# MCU.net
KiCad netlist of a schematic drawn in Altium Designer
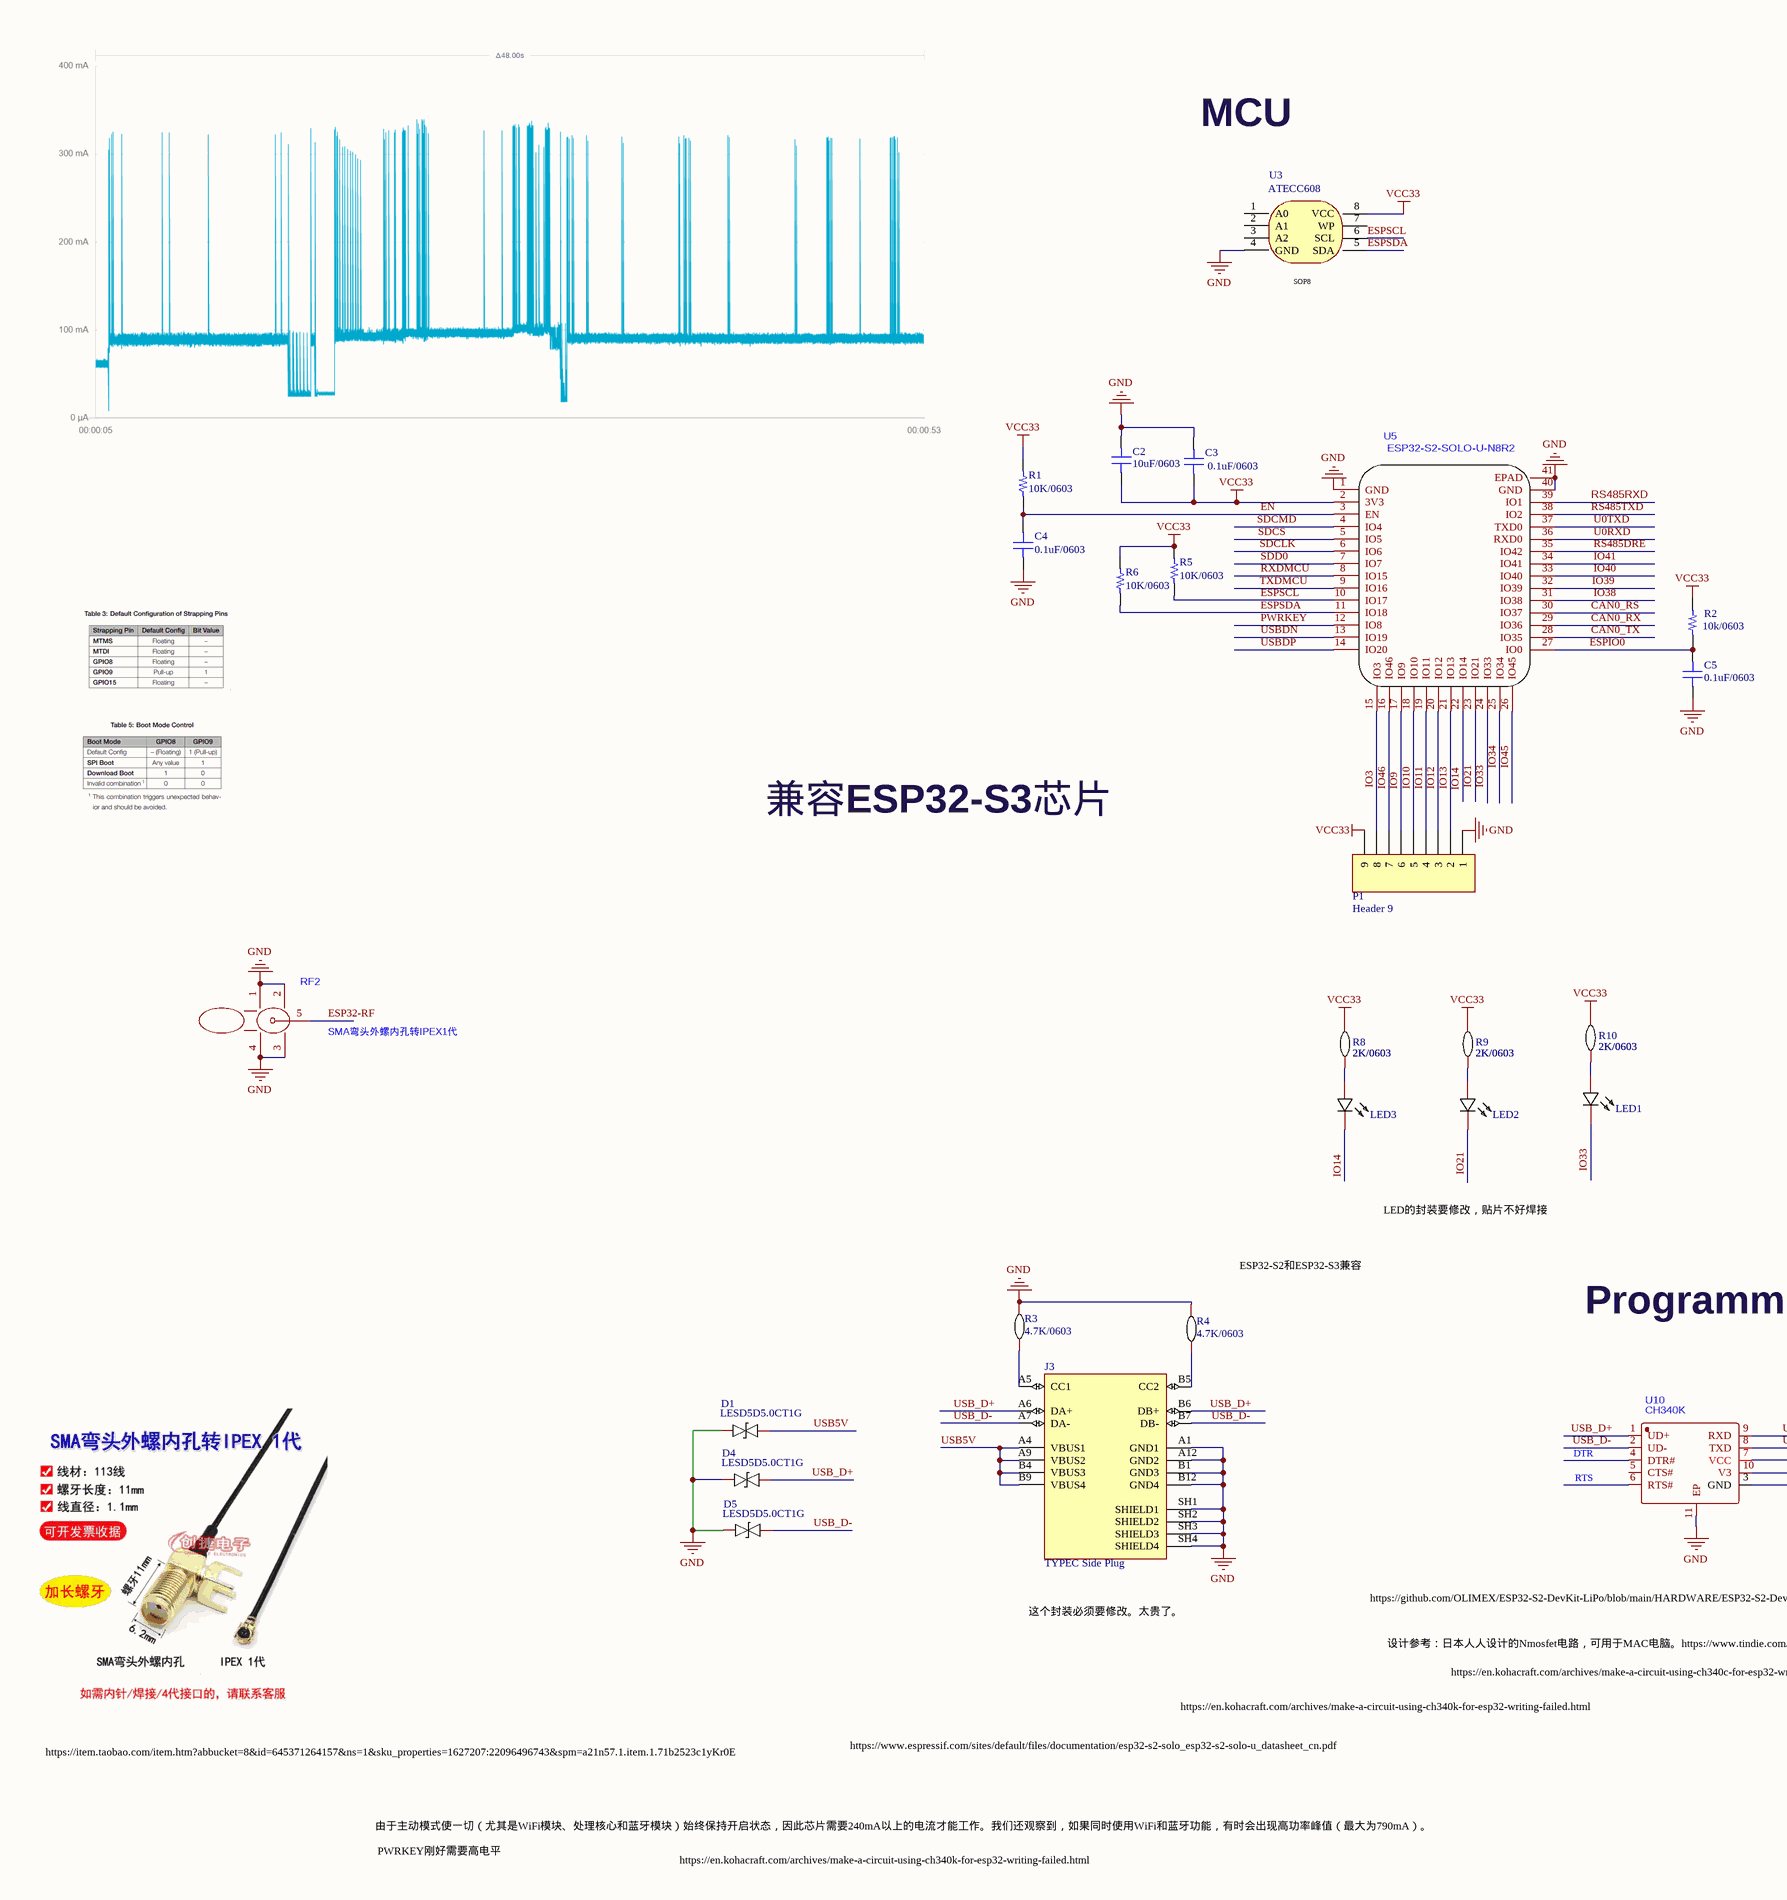
[diagram p0: MCU.SchDoc, left]
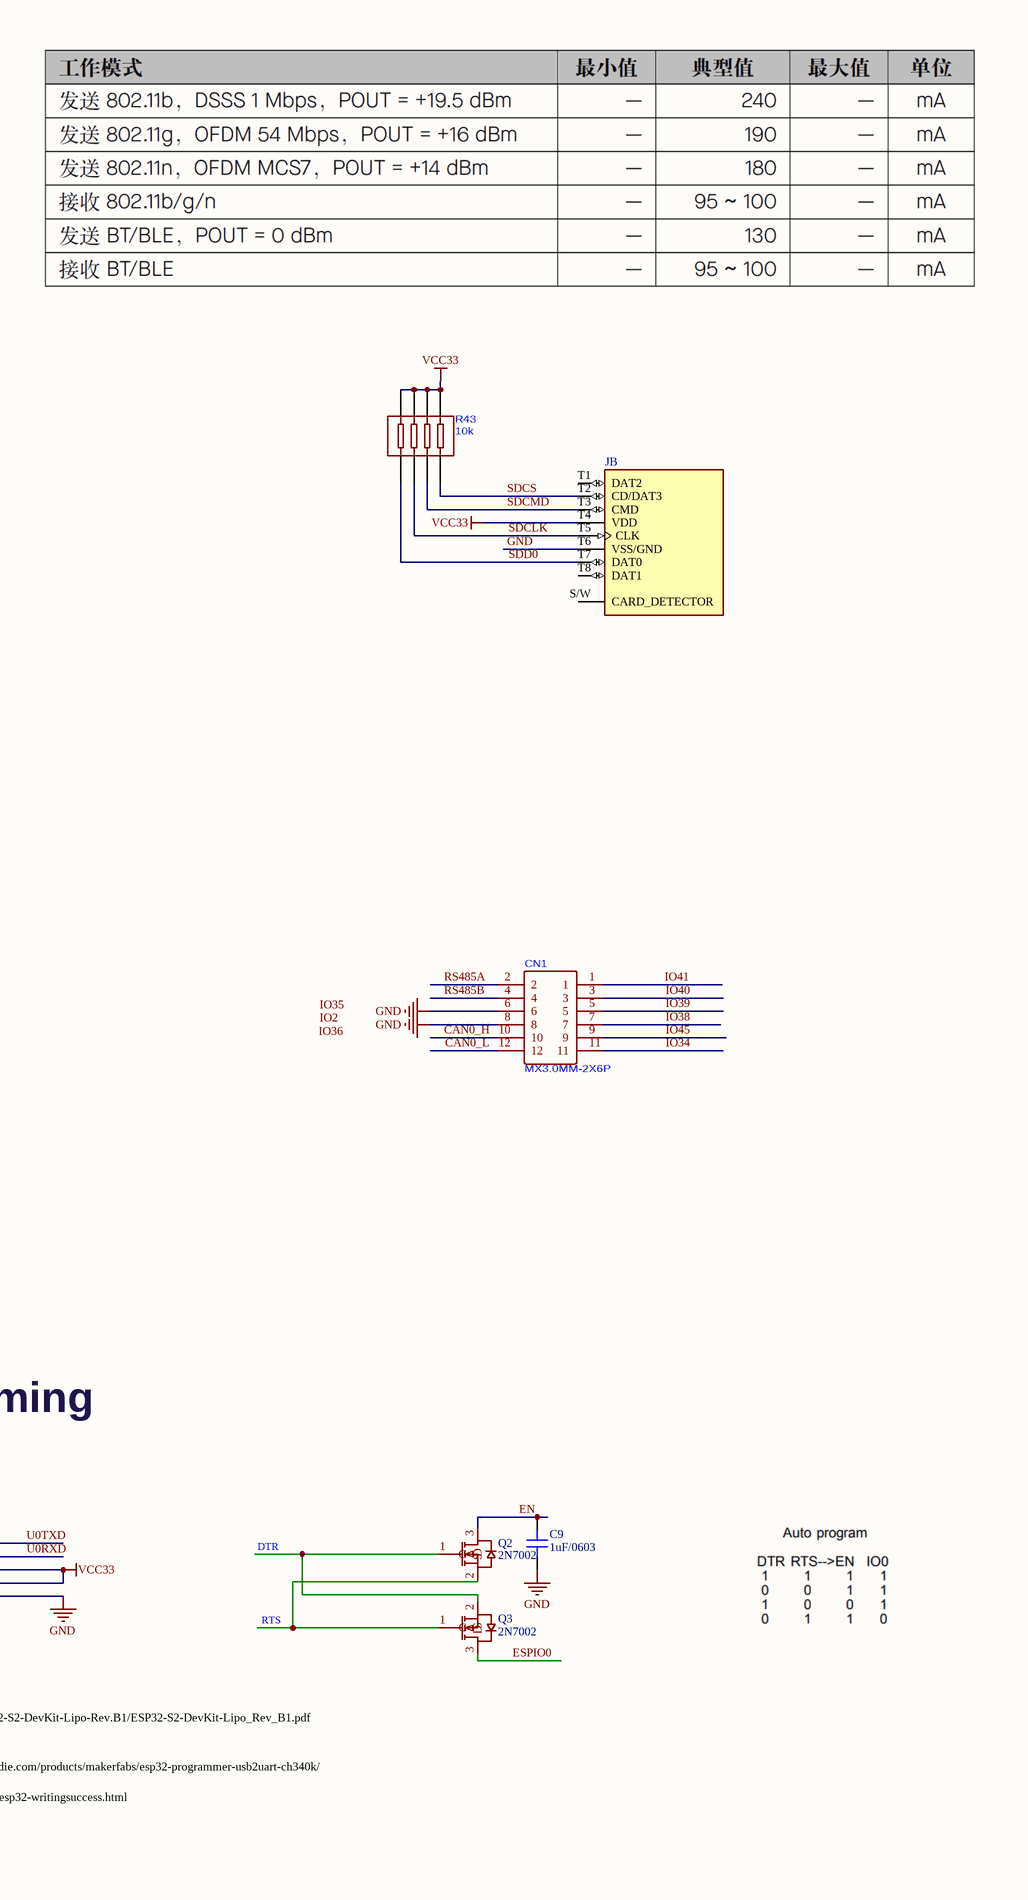
[diagram p1: MCU.SchDoc, right]

(export (version "E")
  (design (tool "Eeschema 10.0.6"))
  (components
    (comp (ref "C2")
      (value "10uF/0603")
      (footprint "CAP0603")
      (description "CAP CER SMD 0805 22PF 5% 50V X7R")
      (fields (field (name "PART NUMBER") "C0805C220J5RAC7800") (field (name "MANUFACTURER") "KEMET"))
      (libsource (lib "Celestial Altium Library - altium_library") (part "Capacitor"))
    )
    (comp (ref "C3")
      (value "0.1uF/0603")
      (footprint "CAp0603")
      (description "CAP CER SMD 0805 22PF 5% 50V X7R")
      (fields (field (name "PART NUMBER") "C0805C220J5RAC7800") (field (name "MANUFACTURER") "KEMET"))
      (libsource (lib "Celestial Altium Library - altium_library") (part "Capacitor"))
    )
    (comp (ref "C4")
      (value "0.1uF/0603")
      (footprint "CAP0603")
      (description "CAP CER SMD 0805 22PF 5% 50V X7R")
      (fields (field (name "PART NUMBER") "C0805C220J5RAC7800") (field (name "MANUFACTURER") "KEMET"))
      (libsource (lib "Celestial Altium Library - altium_library") (part "Capacitor"))
    )
    (comp (ref "C5")
      (value "0.1uF/0603")
      (footprint "CAP0603")
      (description "CAP CER SMD 0805 22PF 5% 50V X7R")
      (fields (field (name "PART NUMBER") "C0805C220J5RAC7800") (field (name "MANUFACTURER") "KEMET"))
      (libsource (lib "Celestial Altium Library - altium_library") (part "Capacitor"))
    )
    (comp (ref "C9")
      (value "1uF/0603")
      (footprint "CAP0603")
      (description "CAP CER SMD 0805 22PF 5% 50V X7R")
      (fields (field (name "PART NUMBER") "C0805C220J5RAC7800") (field (name "MANUFACTURER") "KEMET"))
      (libsource (lib "Celestial Altium Library - altium_library") (part "Capacitor"))
    )
    (comp (ref "CN1")
      (value "MX3.0MM-2X6P")
      (footprint "3.0MM-2X6P")
      (libsource (lib "mySCH") (part "A2005WR-2X6P"))
    )
    (comp (ref "D1")
      (value "LESD5D5.0CT1G")
      (footprint "LESD5D5.0CT1G-SOD-523")
      (description "Bi-Directional 5V SOD-523 Electrostatic and Surge Protection")
      (fields (field (name "NAME") "LESD5D5.0CT1G") (field (name "MANUFACTURER") "Leshan Radio"))
      (libsource (lib "altium-import") (part "root_2_LESD5D5.0CT1G_"))
    )
    (comp (ref "D4")
      (value "LESD5D5.0CT1G")
      (footprint "LESD5D5.0CT1G-SOD-523")
      (description "Bi-Directional 5V SOD-523 Electrostatic and Surge Protection")
      (fields (field (name "NAME") "LESD5D5.0CT1G") (field (name "MANUFACTURER") "Leshan Radio"))
      (libsource (lib "altium-import") (part "root_2_LESD5D5.0CT1G_"))
    )
    (comp (ref "D5")
      (value "LESD5D5.0CT1G")
      (footprint "LESD5D5.0CT1G-SOD-523")
      (description "Bi-Directional 5V SOD-523 Electrostatic and Surge Protection")
      (fields (field (name "NAME") "LESD5D5.0CT1G") (field (name "MANUFACTURER") "Leshan Radio"))
      (libsource (lib "altium-import") (part "root_2_LESD5D5.0CT1G_"))
    )
    (comp (ref "J")
      (value "104642-1610")
      (footprint "MOLEX_104642-1610")
      (fields (field (name "MF") "Molex"))
      (libsource (lib "ESPC6IOTALLinOne") (part "104642-1610"))
    )
    (comp (ref "J3")
      (value "TYPEC Side Plug")
      (footprint "TYPE-C side plug")
      (fields (field (name "MF") "{'manufacturer': u'Molex'}") (field (name "MP") "2169890001"))
      (libsource (lib "mySCH") (part "TYPEC Side Plug"))
    )
    (comp (ref "LED1")
      (value "0603LED-红")
      (footprint "LED_0603_KA")
      (description "0603LED-红，兼容直插")
      (fields
        (field (name "MANUFACTURER") "EVERLIGHT")
        (field (name "MANUFACTURER PART") "19-217/GHC-YR1S2/3T")
      )
      (libsource (lib "mySCH") (part "LED"))
    )
    (comp (ref "LED2")
      (value "0603LED-红")
      (footprint "LED_0603_KA")
      (description "0603LED-红，兼容直插")
      (fields
        (field (name "MANUFACTURER") "EVERLIGHT")
        (field (name "MANUFACTURER PART") "19-217/GHC-YR1S2/3T")
      )
      (libsource (lib "mySCH") (part "LED"))
    )
    (comp (ref "LED3")
      (value "0603LED-红")
      (footprint "LED_0603_KA")
      (description "0603LED-红，兼容直插")
      (fields
        (field (name "MANUFACTURER") "EVERLIGHT")
        (field (name "MANUFACTURER PART") "19-217/GHC-YR1S2/3T")
      )
      (libsource (lib "mySCH") (part "LED"))
    )
    (comp (ref "P1")
      (value "Header 9")
      (footprint "HDR1X9")
      (description "Header, 9-Pin")
      (fields (field (name "PUBLISHER") "Altium Limited"))
      (libsource (lib "Miscellaneous Connectors") (part "Header 9"))
    )
    (comp (ref "Q2")
      (value "2N7002")
      (footprint "SOT-23_2N7002")
      (description "Nmos 2N7000, 2N7002, NDS7002A")
      (libsource (lib "ChargingPile") (part "2N7002"))
    )
    (comp (ref "Q3")
      (value "2N7002")
      (footprint "SOT-23_2N7002")
      (description "Nmos 2N7000, 2N7002, NDS7002A")
      (libsource (lib "ChargingPile") (part "2N7002"))
    )
    (comp (ref "R1")
      (value "10K/0603")
      (footprint "RES0603")
      (description "RES, PULSE, 0805, 5%, 100 OHM, 0")
      (fields
        (field (name "PART NUMBER") "RPC0805JT100R-UP")
        (field (name "MANUFACTURER") "Stackpole Electronics Inc")
      )
      (libsource (lib "Celestial Altium Library - altium_library") (part "Resistor"))
    )
    (comp (ref "R2")
      (value "10k/0603")
      (footprint "RES0603")
      (description "RES, PULSE, 0805, 5%, 100 OHM, 0")
      (fields
        (field (name "PART NUMBER") "RPC0805JT100R-UP")
        (field (name "MANUFACTURER") "Stackpole Electronics Inc")
      )
      (libsource (lib "Celestial Altium Library - altium_library") (part "Resistor"))
    )
    (comp (ref "R3")
      (value "4.7K/0603")
      (footprint "RES0603")
      (fields (field (name "MANUFACTURER") "UniOhm") (field (name "MANUFACTURER PART") "0402WGF5101TCE"))
      (libsource (lib "altium-import") (part "root_3_5.1K_"))
    )
    (comp (ref "R4")
      (value "4.7K/0603")
      (footprint "RES0603")
      (fields (field (name "MANUFACTURER") "UniOhm") (field (name "MANUFACTURER PART") "0402WGF5101TCE"))
      (libsource (lib "altium-import") (part "root_3_5.1K_"))
    )
    (comp (ref "R5")
      (value "10K/0603")
      (footprint "RES0603")
      (description "RES, PULSE, 0805, 5%, 100 OHM, 0")
      (fields
        (field (name "PART NUMBER") "RPC0805JT100R-UP")
        (field (name "MANUFACTURER") "Stackpole Electronics Inc")
      )
      (libsource (lib "Celestial Altium Library - altium_library") (part "Resistor"))
    )
    (comp (ref "R6")
      (value "10K/0603")
      (footprint "RES0603")
      (description "RES, PULSE, 0805, 5%, 100 OHM, 0")
      (fields
        (field (name "PART NUMBER") "RPC0805JT100R-UP")
        (field (name "MANUFACTURER") "Stackpole Electronics Inc")
      )
      (libsource (lib "Celestial Altium Library - altium_library") (part "Resistor"))
    )
    (comp (ref "R8")
      (value "2K/0603")
      (footprint "RES0603")
      (fields
        (field (name "NAME") "2K/0603")
        (field (name "MANUFACTURER") "UniOhm")
        (field (name "MANUFACTURER PART") "0402WGF2201TCE")
      )
      (libsource (lib "altium-import") (part "root_3_2.2K_"))
    )
    (comp (ref "R9")
      (value "2K/0603")
      (footprint "RES0603")
      (fields
        (field (name "NAME") "2K/0603")
        (field (name "MANUFACTURER") "UniOhm")
        (field (name "MANUFACTURER PART") "0402WGF2201TCE")
      )
      (libsource (lib "altium-import") (part "root_3_2.2K_"))
    )
    (comp (ref "R10")
      (value "2K/0603")
      (footprint "RES0603")
      (fields
        (field (name "NAME") "2K/0603")
        (field (name "MANUFACTURER") "UniOhm")
        (field (name "MANUFACTURER PART") "0402WGF2201TCE")
      )
      (libsource (lib "altium-import") (part "root_3_2.2K_"))
    )
    (comp (ref "R43")
      (value "10k")
      (footprint "RES-ARRAY-SMD_8P-L3.2-W1.6-P0.80-BL")
      (description "电阻排-4D03")
      (libsource (lib "altium-import") (part "root_0_mirrored_2.2K排阻-4D03_"))
    )
    (comp (ref "RF2")
      (value "SMA弯头外螺内孔转IPEX1代")
      (footprint "SMA-TH_BWSMA-KWE-Z001")
      (libsource (lib "altium-import") (part "root_1_BWSMA-KWE-Z001_"))
    )
    (comp (ref "U3")
      (value "ATECC608")
      (footprint "SOIC127P600X175-8N - duplicate")
      (description "microchip 加密芯片 IIC，SOIC封装")
      (libsource (lib "TCU+ID") (part "24CXX"))
    )
    (comp (ref "U5")
      (value "ESP32-S2-SOLO-U-N8R2")
      (footprint "ESP32-S2-SOLO-U")
      (description "RISC-V芯片或Xtensa双核芯片,wifi+BLE.腿脚兼容ESP32-S3")
      (libsource (lib "altium-import") (part "root_0_ESP32-S2-SOLO-U-N4_"))
    )
    (comp (ref "U10")
      (value "CH340K")
      (footprint "ESOP-10_L4.9-W3.9-P1.00-LS6.2-BL-EP CH340K")
      (description "usb转串口，用于下载使用。")
      (libsource (lib "mySCH") (part "CH340K"))
    )
  )
  (nets
    (net (code "1") (name "/CAN0_H") (class "Default")
      (node (ref "CN1") (pin "10") (pinfunction "10_10") (pintype "passive"))
    )
    (net (code "2") (name "/CAN0_L") (class "Default")
      (node (ref "CN1") (pin "12") (pinfunction "12_12") (pintype "passive"))
    )
    (net (code "3") (name "/CAN0_RS") (class "Default")
      (node (ref "U5") (pin "30") (pinfunction "IO37_30") (pintype "passive"))
    )
    (net (code "4") (name "/CAN0_RX") (class "Default")
      (node (ref "U5") (pin "29") (pinfunction "IO36_29") (pintype "passive"))
    )
    (net (code "5") (name "/CAN0_TX") (class "Default")
      (node (ref "U5") (pin "28") (pinfunction "IO35_28") (pintype "passive"))
    )
    (net (code "6") (name "/DTR") (class "Default")
      (node (ref "Q2") (pin "1") (pinfunction "G_1") (pintype "passive"))
      (node (ref "Q3") (pin "2") (pinfunction "S_2") (pintype "passive"))
      (node (ref "U10") (pin "4") (pinfunction "DTR#_4") (pintype "passive"))
    )
    (net (code "7") (name "/EN") (class "Default")
      (node (ref "C4") (pin "2") (pinfunction "2_2") (pintype "passive"))
      (node (ref "C9") (pin "2") (pinfunction "2_2") (pintype "passive"))
      (node (ref "Q2") (pin "3") (pinfunction "D_3") (pintype "passive"))
      (node (ref "R1") (pin "1") (pinfunction "1_1") (pintype "passive"))
      (node (ref "U5") (pin "3") (pinfunction "EN_3") (pintype "passive"))
    )
    (net (code "8") (name "/ESP32-RF") (class "Default")
      (node (ref "RF2") (pin "5") (pinfunction "5_5") (pintype "passive"))
    )
    (net (code "9") (name "/ESPIO0") (class "Default")
      (node (ref "C5") (pin "2") (pinfunction "2_2") (pintype "passive"))
      (node (ref "Q3") (pin "3") (pinfunction "D_3") (pintype "passive"))
      (node (ref "R2") (pin "1") (pinfunction "1_1") (pintype "passive"))
      (node (ref "U5") (pin "27") (pinfunction "IO0_27") (pintype "passive"))
    )
    (net (code "10") (name "/ESPSCL") (class "Default")
      (node (ref "R5") (pin "1") (pinfunction "1_1") (pintype "passive"))
      (node (ref "U3") (pin "6") (pinfunction "SCL_6") (pintype "passive"))
      (node (ref "U5") (pin "10") (pinfunction "IO17_10") (pintype "passive"))
    )
    (net (code "11") (name "/ESPSDA") (class "Default")
      (node (ref "R6") (pin "1") (pinfunction "1_1") (pintype "passive"))
      (node (ref "U3") (pin "5") (pinfunction "SDA_5") (pintype "passive"))
      (node (ref "U5") (pin "11") (pinfunction "IO18_11") (pintype "passive"))
    )
    (net (code "13") (name "/IO3") (class "Default")
      (node (ref "P1") (pin "8") (pinfunction "8_8") (pintype "passive"))
      (node (ref "U5") (pin "15") (pinfunction "IO3_15") (pintype "passive"))
    )
    (net (code "14") (name "/IO9") (class "Default")
      (node (ref "P1") (pin "6") (pinfunction "6_6") (pintype "passive"))
      (node (ref "U5") (pin "17") (pinfunction "IO9_17") (pintype "passive"))
    )
    (net (code "15") (name "/IO10") (class "Default")
      (node (ref "P1") (pin "5") (pinfunction "5_5") (pintype "passive"))
      (node (ref "U5") (pin "18") (pinfunction "IO10_18") (pintype "passive"))
    )
    (net (code "16") (name "/IO11") (class "Default")
      (node (ref "P1") (pin "4") (pinfunction "4_4") (pintype "passive"))
      (node (ref "U5") (pin "19") (pinfunction "IO11_19") (pintype "passive"))
    )
    (net (code "17") (name "/IO12") (class "Default")
      (node (ref "P1") (pin "3") (pinfunction "3_3") (pintype "passive"))
      (node (ref "U5") (pin "20") (pinfunction "IO12_20") (pintype "passive"))
    )
    (net (code "18") (name "/IO13") (class "Default")
      (node (ref "P1") (pin "2") (pinfunction "2_2") (pintype "passive"))
      (node (ref "U5") (pin "21") (pinfunction "IO13_21") (pintype "passive"))
    )
    (net (code "19") (name "/IO14") (class "Default")
      (node (ref "LED3") (pin "2") (pinfunction "C_2") (pintype "passive"))
      (node (ref "U5") (pin "22") (pinfunction "IO14_22") (pintype "passive"))
    )
    (net (code "20") (name "/IO21") (class "Default")
      (node (ref "LED2") (pin "2") (pinfunction "C_2") (pintype "passive"))
      (node (ref "U5") (pin "23") (pinfunction "IO21_23") (pintype "passive"))
    )
    (net (code "21") (name "/IO33") (class "Default")
      (node (ref "LED1") (pin "2") (pinfunction "C_2") (pintype "passive"))
      (node (ref "U5") (pin "24") (pinfunction "IO33_24") (pintype "passive"))
    )
    (net (code "22") (name "/IO34") (class "Default")
      (node (ref "CN1") (pin "11") (pinfunction "11_11") (pintype "passive"))
      (node (ref "U5") (pin "25") (pinfunction "IO34_25") (pintype "passive"))
    )
    (net (code "25") (name "/IO38") (class "Default")
      (node (ref "CN1") (pin "7") (pinfunction "7_7") (pintype "passive"))
      (node (ref "U5") (pin "31") (pinfunction "IO38_31") (pintype "passive"))
    )
    (net (code "26") (name "/IO39") (class "Default")
      (node (ref "CN1") (pin "5") (pinfunction "5_5") (pintype "passive"))
      (node (ref "U5") (pin "32") (pinfunction "IO39_32") (pintype "passive"))
    )
    (net (code "27") (name "/IO40") (class "Default")
      (node (ref "CN1") (pin "3") (pinfunction "3_3") (pintype "passive"))
      (node (ref "U5") (pin "33") (pinfunction "IO40_33") (pintype "passive"))
    )
    (net (code "28") (name "/IO41") (class "Default")
      (node (ref "CN1") (pin "1") (pinfunction "1_1") (pintype "passive"))
      (node (ref "U5") (pin "34") (pinfunction "IO41_34") (pintype "passive"))
    )
    (net (code "29") (name "/IO45") (class "Default")
      (node (ref "CN1") (pin "9") (pinfunction "9_9") (pintype "passive"))
      (node (ref "U5") (pin "26") (pinfunction "IO45_26") (pintype "passive"))
    )
    (net (code "30") (name "/IO46") (class "Default")
      (node (ref "P1") (pin "7") (pinfunction "7_7") (pintype "passive"))
      (node (ref "U5") (pin "16") (pinfunction "IO46_16") (pintype "passive"))
    )
    (net (code "31") (name "/PWRKEY") (class "Default")
      (node (ref "U5") (pin "12") (pinfunction "IO8_12") (pintype "passive"))
    )
    (net (code "32") (name "/RS485A") (class "Default")
      (node (ref "CN1") (pin "2") (pinfunction "2_2") (pintype "passive"))
    )
    (net (code "33") (name "/RS485B") (class "Default")
      (node (ref "CN1") (pin "4") (pinfunction "4_4") (pintype "passive"))
    )
    (net (code "34") (name "/RS485DRE") (class "Default")
      (node (ref "U5") (pin "35") (pinfunction "IO42_35") (pintype "passive"))
    )
    (net (code "35") (name "/RS485RXD") (class "Default")
      (node (ref "U5") (pin "39") (pinfunction "IO1_39") (pintype "passive"))
    )
    (net (code "36") (name "/RS485TXD") (class "Default")
      (node (ref "U5") (pin "38") (pinfunction "IO2_38") (pintype "passive"))
    )
    (net (code "37") (name "/RTS") (class "Default")
      (node (ref "Q2") (pin "2") (pinfunction "S_2") (pintype "passive"))
      (node (ref "Q3") (pin "1") (pinfunction "G_1") (pintype "passive"))
      (node (ref "U10") (pin "6") (pinfunction "RTS#_6") (pintype "passive"))
    )
    (net (code "38") (name "/RXDMCU") (class "Default")
      (node (ref "U5") (pin "8") (pinfunction "IO15_8") (pintype "passive"))
    )
    (net (code "39") (name "/SDCLK") (class "Default")
      (node (ref "J") (pin "T5") (pinfunction "CLK_T5") (pintype "input"))
      (node (ref "R43") (pin "3") (pinfunction "3_3") (pintype "passive"))
      (node (ref "U5") (pin "6") (pinfunction "IO6_6") (pintype "passive"))
    )
    (net (code "40") (name "/SDCMD") (class "Default")
      (node (ref "J") (pin "T3") (pinfunction "CMD_T3") (pintype "bidirectional"))
      (node (ref "R43") (pin "2") (pinfunction "2_2") (pintype "passive"))
      (node (ref "U5") (pin "4") (pinfunction "IO4_4") (pintype "passive"))
    )
    (net (code "41") (name "/SDCS") (class "Default")
      (node (ref "J") (pin "T2") (pinfunction "CD/DAT3_T2") (pintype "bidirectional"))
      (node (ref "R43") (pin "1") (pinfunction "1_1") (pintype "passive"))
      (node (ref "U5") (pin "5") (pinfunction "IO5_5") (pintype "passive"))
    )
    (net (code "42") (name "/SDD0") (class "Default")
      (node (ref "J") (pin "T7") (pinfunction "DAT0_T7") (pintype "bidirectional"))
      (node (ref "R43") (pin "4") (pinfunction "4_4") (pintype "passive"))
      (node (ref "U5") (pin "7") (pinfunction "IO7_7") (pintype "passive"))
    )
    (net (code "43") (name "/TXDMCU") (class "Default")
      (node (ref "U5") (pin "9") (pinfunction "IO16_9") (pintype "passive"))
    )
    (net (code "44") (name "/U0RXD") (class "Default")
      (node (ref "U10") (pin "8") (pinfunction "TXD_8") (pintype "passive"))
      (node (ref "U5") (pin "36") (pinfunction "RXD0_36") (pintype "passive"))
    )
    (net (code "45") (name "/U0TXD") (class "Default")
      (node (ref "U10") (pin "9") (pinfunction "RXD_9") (pintype "passive"))
      (node (ref "U5") (pin "37") (pinfunction "TXD0_37") (pintype "passive"))
    )
    (net (code "46") (name "/USB5V") (class "Default")
      (node (ref "D1") (pin "1") (pinfunction "1_1") (pintype "passive"))
      (node (ref "J3") (pin "A4") (pinfunction "VBUS1_A4") (pintype "power_in"))
      (node (ref "J3") (pin "A9") (pinfunction "VBUS2_A9") (pintype "power_in"))
      (node (ref "J3") (pin "B4") (pinfunction "VBUS3_B4") (pintype "power_in"))
      (node (ref "J3") (pin "B9") (pinfunction "VBUS4_B9") (pintype "power_in"))
    )
    (net (code "47") (name "/USBDN") (class "Default")
      (node (ref "U5") (pin "13") (pinfunction "IO19_13") (pintype "passive"))
    )
    (net (code "48") (name "/USBDP") (class "Default")
      (node (ref "U5") (pin "14") (pinfunction "IO20_14") (pintype "passive"))
    )
    (net (code "49") (name "/USB_D+") (class "Default")
      (node (ref "D4") (pin "1") (pinfunction "1_1") (pintype "passive"))
      (node (ref "J3") (pin "A6") (pinfunction "DA+_A6") (pintype "bidirectional"))
      (node (ref "J3") (pin "B6") (pinfunction "DB+_B6") (pintype "bidirectional"))
      (node (ref "U10") (pin "1") (pinfunction "UD+_1") (pintype "passive"))
    )
    (net (code "50") (name "/USB_D-") (class "Default")
      (node (ref "D5") (pin "1") (pinfunction "1_1") (pintype "passive"))
      (node (ref "J3") (pin "A7") (pinfunction "DA-_A7") (pintype "bidirectional"))
      (node (ref "J3") (pin "B7") (pinfunction "DB-_B7") (pintype "bidirectional"))
      (node (ref "U10") (pin "2") (pinfunction "UD-_2") (pintype "passive"))
    )
    (net (code "51") (name "GND") (class "Default")
      (node (ref "C2") (pin "1") (pinfunction "1_1") (pintype "passive"))
      (node (ref "C3") (pin "1") (pinfunction "1_1") (pintype "passive"))
      (node (ref "C4") (pin "1") (pinfunction "1_1") (pintype "passive"))
      (node (ref "C5") (pin "1") (pinfunction "1_1") (pintype "passive"))
      (node (ref "C9") (pin "1") (pinfunction "1_1") (pintype "passive"))
      (node (ref "CN1") (pin "6") (pinfunction "6_6") (pintype "passive"))
      (node (ref "CN1") (pin "8") (pinfunction "8_8") (pintype "passive"))
      (node (ref "D1") (pin "2") (pinfunction "2_2") (pintype "passive"))
      (node (ref "D4") (pin "2") (pinfunction "2_2") (pintype "passive"))
      (node (ref "D5") (pin "2") (pinfunction "2_2") (pintype "passive"))
      (node (ref "J") (pin "T6") (pinfunction "VSS/GND_T6") (pintype "power_in"))
      (node (ref "J3") (pin "A1") (pinfunction "GND1_A1") (pintype "power_in"))
      (node (ref "J3") (pin "A12") (pinfunction "GND2_A12") (pintype "power_in"))
      (node (ref "J3") (pin "B1") (pinfunction "GND3_B1") (pintype "power_in"))
      (node (ref "J3") (pin "B12") (pinfunction "GND4_B12") (pintype "power_in"))
      (node (ref "J3") (pin "SH1") (pinfunction "SHIELD1_SH1") (pintype "passive"))
      (node (ref "J3") (pin "SH2") (pinfunction "SHIELD2_SH2") (pintype "passive"))
      (node (ref "J3") (pin "SH3") (pinfunction "SHIELD3_SH3") (pintype "passive"))
      (node (ref "J3") (pin "SH4") (pinfunction "SHIELD4_SH4") (pintype "passive"))
      (node (ref "P1") (pin "1") (pinfunction "1_1") (pintype "passive"))
      (node (ref "R3") (pin "1") (pinfunction "1_1") (pintype "passive"))
      (node (ref "R4") (pin "1") (pinfunction "1_1") (pintype "passive"))
      (node (ref "RF2") (pin "1") (pinfunction "1_1") (pintype "passive"))
      (node (ref "RF2") (pin "2") (pinfunction "2_2") (pintype "passive"))
      (node (ref "RF2") (pin "3") (pinfunction "3_3") (pintype "passive"))
      (node (ref "RF2") (pin "4") (pinfunction "4_4") (pintype "passive"))
      (node (ref "U10") (pin "11") (pinfunction "EP_11") (pintype "passive"))
      (node (ref "U10") (pin "3") (pinfunction "GND_3") (pintype "passive"))
      (node (ref "U3") (pin "4") (pinfunction "GND_4") (pintype "passive"))
      (node (ref "U5") (pin "1") (pinfunction "GND_1") (pintype "passive"))
      (node (ref "U5") (pin "40") (pinfunction "GND_40") (pintype "passive"))
      (node (ref "U5") (pin "41") (pinfunction "EPAD_41") (pintype "passive"))
    )
    (net (code "52") (name "Net-(J3-CC1)") (class "Default")
      (node (ref "J3") (pin "A5") (pinfunction "CC1_A5") (pintype "bidirectional"))
      (node (ref "R3") (pin "2") (pinfunction "2_2") (pintype "passive"))
    )
    (net (code "53") (name "Net-(J3-CC2)") (class "Default")
      (node (ref "J3") (pin "B5") (pinfunction "CC2_B5") (pintype "bidirectional"))
      (node (ref "R4") (pin "2") (pinfunction "2_2") (pintype "passive"))
    )
    (net (code "54") (name "Net-(LED1-A)") (class "Default")
      (node (ref "LED1") (pin "1") (pinfunction "A_1") (pintype "passive"))
      (node (ref "R10") (pin "2") (pinfunction "2_2") (pintype "passive"))
    )
    (net (code "55") (name "Net-(LED2-A)") (class "Default")
      (node (ref "LED2") (pin "1") (pinfunction "A_1") (pintype "passive"))
      (node (ref "R9") (pin "2") (pinfunction "2_2") (pintype "passive"))
    )
    (net (code "56") (name "Net-(LED3-A)") (class "Default")
      (node (ref "LED3") (pin "1") (pinfunction "A_1") (pintype "passive"))
      (node (ref "R8") (pin "2") (pinfunction "2_2") (pintype "passive"))
    )
    (net (code "57") (name "VCC33") (class "Default")
      (node (ref "C2") (pin "2") (pinfunction "2_2") (pintype "passive"))
      (node (ref "C3") (pin "2") (pinfunction "2_2") (pintype "passive"))
      (node (ref "J") (pin "T4") (pinfunction "VDD_T4") (pintype "power_in"))
      (node (ref "P1") (pin "9") (pinfunction "9_9") (pintype "passive"))
      (node (ref "R1") (pin "2") (pinfunction "2_2") (pintype "passive"))
      (node (ref "R10") (pin "1") (pinfunction "1_1") (pintype "passive"))
      (node (ref "R2") (pin "2") (pinfunction "2_2") (pintype "passive"))
      (node (ref "R43") (pin "5") (pinfunction "5_5") (pintype "passive"))
      (node (ref "R43") (pin "6") (pinfunction "6_6") (pintype "passive"))
      (node (ref "R43") (pin "7") (pinfunction "7_7") (pintype "passive"))
      (node (ref "R43") (pin "8") (pinfunction "8_8") (pintype "passive"))
      (node (ref "R5") (pin "2") (pinfunction "2_2") (pintype "passive"))
      (node (ref "R6") (pin "2") (pinfunction "2_2") (pintype "passive"))
      (node (ref "R8") (pin "1") (pinfunction "1_1") (pintype "passive"))
      (node (ref "R9") (pin "1") (pinfunction "1_1") (pintype "passive"))
      (node (ref "U10") (pin "10") (pinfunction "V3_10") (pintype "passive"))
      (node (ref "U10") (pin "7") (pinfunction "VCC_7") (pintype "passive"))
      (node (ref "U3") (pin "8") (pinfunction "VCC_8") (pintype "passive"))
      (node (ref "U5") (pin "2") (pinfunction "3V3_2") (pintype "passive"))
    )
    (net (code "58") (name "unconnected-(JB-CARD_DETECTOR-PadS{slash}W)") (class "Default")
      (node (ref "J") (pin "S/W") (pinfunction "CARD_DETECTOR_S/W") (pintype "passive"))
    )
    (net (code "59") (name "unconnected-(JB-DAT1-PadT8)") (class "Default")
      (node (ref "J") (pin "T8") (pinfunction "DAT1_T8") (pintype "bidirectional"))
    )
    (net (code "60") (name "unconnected-(JB-DAT2-PadT1)") (class "Default")
      (node (ref "J") (pin "T1") (pinfunction "DAT2_T1") (pintype "bidirectional"))
    )
    (net (code "61") (name "unconnected-(U3-A0-Pad1)") (class "Default")
      (node (ref "U3") (pin "1") (pinfunction "A0_1") (pintype "passive"))
    )
    (net (code "62") (name "unconnected-(U3-A1-Pad2)") (class "Default")
      (node (ref "U3") (pin "2") (pinfunction "A1_2") (pintype "passive"))
    )
    (net (code "63") (name "unconnected-(U3-A2-Pad3)") (class "Default")
      (node (ref "U3") (pin "3") (pinfunction "A2_3") (pintype "passive"))
    )
    (net (code "64") (name "unconnected-(U3-WP-Pad7)") (class "Default")
      (node (ref "U3") (pin "7") (pinfunction "WP_7") (pintype "passive"))
    )
    (net (code "65") (name "unconnected-(U10-CTS#-Pad5)") (class "Default")
      (node (ref "U10") (pin "5") (pinfunction "CTS#_5") (pintype "passive"))
    )
  )
)
